# untitled.net
KiCad netlist of a schematic drawn in EAGLE
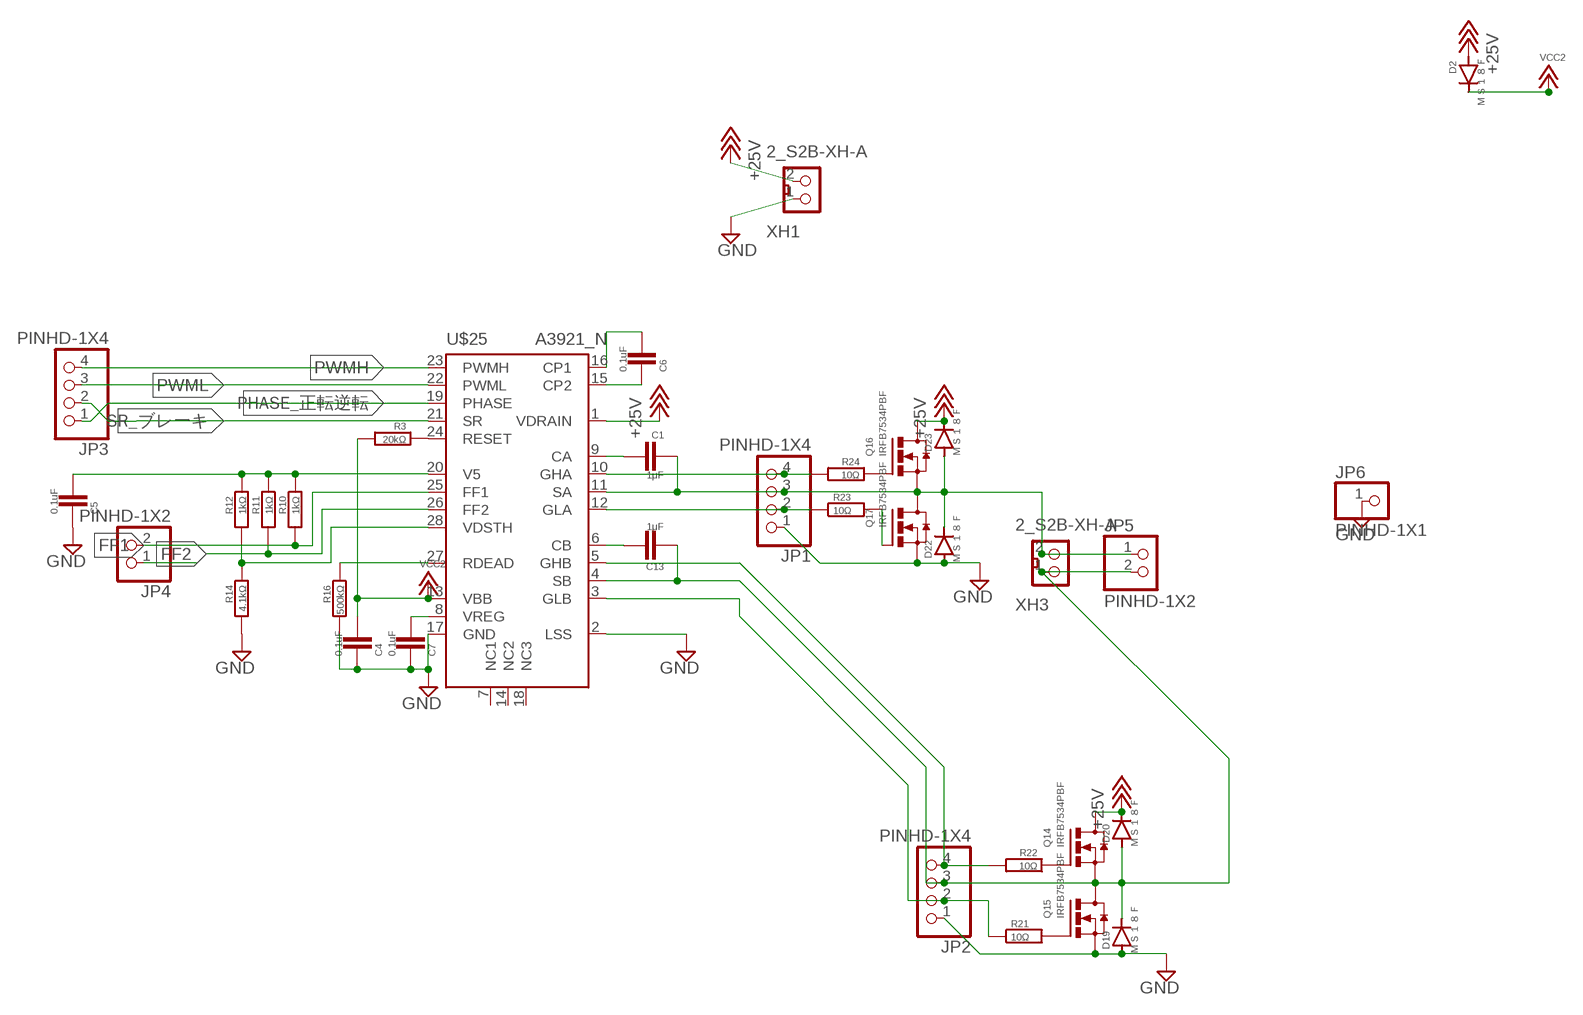
[diagram p0: schematic, sheet 1]

(export (version "E")
  (design (tool "Eeschema 10.0.6"))
  (components
    (comp (ref "C1")
      (value "1μF")
      (footprint "eagle-import:2012")
      (libsource (lib "eagle-import") (part "CAPACITOR{gt}{gt}2012"))
    )
    (comp (ref "C4")
      (value "0.1uF")
      (footprint "eagle-import:2012")
      (libsource (lib "eagle-import") (part "CAPACITOR{gt}{gt}2012"))
    )
    (comp (ref "C5")
      (value "0.1uF")
      (footprint "eagle-import:2012")
      (libsource (lib "eagle-import") (part "CAPACITOR{gt}{gt}2012"))
    )
    (comp (ref "C6")
      (value "0.1uF")
      (footprint "eagle-import:2012")
      (libsource (lib "eagle-import") (part "CAPACITOR{gt}{gt}2012"))
    )
    (comp (ref "C7")
      (value "0.1uF")
      (footprint "eagle-import:2012")
      (libsource (lib "eagle-import") (part "CAPACITOR{gt}{gt}2012"))
    )
    (comp (ref "C13")
      (value "1μF")
      (footprint "eagle-import:2012")
      (libsource (lib "eagle-import") (part "CAPACITOR{gt}{gt}2012"))
    )
    (comp (ref "D2")
      (value "ＭＳ１８Ｆ")
      (footprint "eagle-import:MS18F")
      (libsource (lib "eagle-import") (part "DIODE{gt}{gt}MS18F"))
    )
    (comp (ref "D19")
      (value "ＭＳ１８Ｆ")
      (footprint "eagle-import:MS18F")
      (libsource (lib "eagle-import") (part "DIODE{gt}{gt}MS18F"))
    )
    (comp (ref "D20")
      (value "ＭＳ１８Ｆ")
      (footprint "eagle-import:MS18F")
      (libsource (lib "eagle-import") (part "DIODE{gt}{gt}MS18F"))
    )
    (comp (ref "D22")
      (value "ＭＳ１８Ｆ")
      (footprint "eagle-import:MS18F")
      (libsource (lib "eagle-import") (part "DIODE{gt}{gt}MS18F"))
    )
    (comp (ref "D23")
      (value "ＭＳ１８Ｆ")
      (footprint "eagle-import:MS18F")
      (libsource (lib "eagle-import") (part "DIODE{gt}{gt}MS18F"))
    )
    (comp (ref "JP1")
      (value "PINHD-1X4")
      (footprint "eagle-import:1X04")
      (libsource (lib "eagle-import") (part "PINHD-1X4"))
    )
    (comp (ref "JP2")
      (value "PINHD-1X4")
      (footprint "eagle-import:1X04")
      (libsource (lib "eagle-import") (part "PINHD-1X4"))
    )
    (comp (ref "JP3")
      (value "PINHD-1X4")
      (footprint "eagle-import:1X04")
      (libsource (lib "eagle-import") (part "PINHD-1X4"))
    )
    (comp (ref "JP4")
      (value "PINHD-1X2")
      (footprint "eagle-import:1X02")
      (libsource (lib "eagle-import") (part "PINHD-1X2"))
    )
    (comp (ref "JP5")
      (value "PINHD-1X2")
      (footprint "eagle-import:1X02")
      (libsource (lib "eagle-import") (part "PINHD-1X2"))
    )
    (comp (ref "JP6")
      (value "PINHD-1X1")
      (footprint "eagle-import:1X01")
      (libsource (lib "eagle-import") (part "PINHD-1X1"))
    )
    (comp (ref "Q14")
      (value "IRFB7534PBF")
      (footprint "eagle-import:TO252")
      (libsource (lib "eagle-import") (part "MOSFET_N{gt}{gt}TO252"))
    )
    (comp (ref "Q15")
      (value "IRFB7534PBF")
      (footprint "eagle-import:TO252")
      (libsource (lib "eagle-import") (part "MOSFET_N{gt}{gt}TO252"))
    )
    (comp (ref "Q16")
      (value "IRFB7534PBF")
      (footprint "eagle-import:TO252")
      (libsource (lib "eagle-import") (part "MOSFET_N{gt}{gt}TO252"))
    )
    (comp (ref "Q17")
      (value "IRFB7534PBF")
      (footprint "eagle-import:TO252")
      (libsource (lib "eagle-import") (part "MOSFET_N{gt}{gt}TO252"))
    )
    (comp (ref "R3")
      (value "20kΩ")
      (footprint "eagle-import:2012")
      (libsource (lib "eagle-import") (part "REGISTER{gt}{gt}2012"))
    )
    (comp (ref "R10")
      (value "1kΩ")
      (footprint "eagle-import:2012")
      (libsource (lib "eagle-import") (part "REGISTER{gt}{gt}2012"))
    )
    (comp (ref "R11")
      (value "1kΩ")
      (footprint "eagle-import:2012")
      (libsource (lib "eagle-import") (part "REGISTER{gt}{gt}2012"))
    )
    (comp (ref "R12")
      (value "1kΩ")
      (footprint "eagle-import:2012")
      (libsource (lib "eagle-import") (part "REGISTER{gt}{gt}2012"))
    )
    (comp (ref "R14")
      (value "4.1kΩ")
      (footprint "eagle-import:2012")
      (libsource (lib "eagle-import") (part "REGISTER{gt}{gt}2012"))
    )
    (comp (ref "R16")
      (value "500kΩ")
      (footprint "eagle-import:2012")
      (libsource (lib "eagle-import") (part "REGISTER{gt}{gt}2012"))
    )
    (comp (ref "R21")
      (value "10Ω")
      (footprint "eagle-import:2012")
      (libsource (lib "eagle-import") (part "REGISTER{gt}{gt}2012"))
    )
    (comp (ref "R22")
      (value "10Ω")
      (footprint "eagle-import:2012")
      (libsource (lib "eagle-import") (part "REGISTER{gt}{gt}2012"))
    )
    (comp (ref "R23")
      (value "10Ω")
      (footprint "eagle-import:2012")
      (libsource (lib "eagle-import") (part "REGISTER{gt}{gt}2012"))
    )
    (comp (ref "R24")
      (value "10Ω")
      (footprint "eagle-import:2012")
      (libsource (lib "eagle-import") (part "REGISTER{gt}{gt}2012"))
    )
    (comp (ref "U$25")
      (value "A3921_N")
      (footprint "eagle-import:TSSOP28_N")
      (libsource (lib "eagle-import") (part "A3921_N"))
    )
    (comp (ref "XH1")
      (value "2_S2B-XH-A")
      (footprint "eagle-import:S2B-XH-A")
      (libsource (lib "eagle-import") (part "2_S2B-XH-A"))
    )
    (comp (ref "XH3")
      (value "2_S2B-XH-A")
      (footprint "eagle-import:S2B-XH-A")
      (libsource (lib "eagle-import") (part "2_S2B-XH-A"))
    )
  )
  (nets
    (net (code "1") (name "+25V") (class "Default")
      (node (ref "D2") (pin "P$1") (pinfunction "A_P$1") (pintype "passive"))
      (node (ref "D20") (pin "P$2") (pinfunction "C_P$2") (pintype "passive"))
      (node (ref "D23") (pin "P$2") (pinfunction "C_P$2") (pintype "passive"))
      (node (ref "Q14") (pin "3") (pinfunction "D_3") (pintype "passive"))
      (node (ref "Q16") (pin "3") (pinfunction "D_3") (pintype "passive"))
      (node (ref "U$25") (pin "1") (pinfunction "VDRAIN_1") (pintype "power_in"))
      (node (ref "XH1") (pin "2") (pinfunction "2_2") (pintype "passive"))
    )
    (net (code "2") (name "FF1") (class "Default")
      (node (ref "JP4") (pin "2") (pinfunction "2_2") (pintype "passive"))
      (node (ref "R10") (pin "2") (pinfunction "2_2") (pintype "passive"))
      (node (ref "U$25") (pin "25") (pinfunction "FF1_25") (pintype "output"))
    )
    (net (code "3") (name "FF2") (class "Default")
      (node (ref "JP4") (pin "1") (pinfunction "1_1") (pintype "passive"))
      (node (ref "R11") (pin "2") (pinfunction "2_2") (pintype "passive"))
      (node (ref "U$25") (pin "26") (pinfunction "FF2_26") (pintype "output"))
    )
    (net (code "4") (name "GND") (class "Default")
      (node (ref "C4") (pin "2") (pinfunction "2_2") (pintype "passive"))
      (node (ref "C5") (pin "2") (pinfunction "2_2") (pintype "passive"))
      (node (ref "C7") (pin "2") (pinfunction "2_2") (pintype "passive"))
      (node (ref "D19") (pin "P$1") (pinfunction "A_P$1") (pintype "passive"))
      (node (ref "D22") (pin "P$1") (pinfunction "A_P$1") (pintype "passive"))
      (node (ref "JP1") (pin "1") (pinfunction "1_1") (pintype "passive"))
      (node (ref "JP2") (pin "1") (pinfunction "1_1") (pintype "passive"))
      (node (ref "JP6") (pin "1") (pinfunction "1_1") (pintype "passive"))
      (node (ref "Q15") (pin "2") (pinfunction "S_2") (pintype "passive"))
      (node (ref "Q17") (pin "2") (pinfunction "S_2") (pintype "passive"))
      (node (ref "R14") (pin "2") (pinfunction "2_2") (pintype "passive"))
      (node (ref "R16") (pin "2") (pinfunction "2_2") (pintype "passive"))
      (node (ref "U$25") (pin "17") (pinfunction "GND_17") (pintype "power_in"))
      (node (ref "U$25") (pin "2") (pinfunction "LSS_2") (pintype "passive"))
      (node (ref "XH1") (pin "1") (pinfunction "1_1") (pintype "passive"))
    )
    (net (code "5") (name "Net-(D19-C)") (class "Default")
      (node (ref "C13") (pin "2") (pinfunction "2_2") (pintype "passive"))
      (node (ref "D19") (pin "P$2") (pinfunction "C_P$2") (pintype "passive"))
      (node (ref "D20") (pin "P$1") (pinfunction "A_P$1") (pintype "passive"))
      (node (ref "JP2") (pin "3") (pinfunction "3_3") (pintype "passive"))
      (node (ref "JP5") (pin "2") (pinfunction "2_2") (pintype "passive"))
      (node (ref "Q14") (pin "2") (pinfunction "S_2") (pintype "passive"))
      (node (ref "Q15") (pin "3") (pinfunction "D_3") (pintype "passive"))
      (node (ref "U$25") (pin "4") (pinfunction "SB_4") (pintype "output"))
      (node (ref "XH3") (pin "1") (pinfunction "1_1") (pintype "passive"))
    )
    (net (code "6") (name "Net-(D22-C)") (class "Default")
      (node (ref "C1") (pin "2") (pinfunction "2_2") (pintype "passive"))
      (node (ref "D22") (pin "P$2") (pinfunction "C_P$2") (pintype "passive"))
      (node (ref "D23") (pin "P$1") (pinfunction "A_P$1") (pintype "passive"))
      (node (ref "JP1") (pin "3") (pinfunction "3_3") (pintype "passive"))
      (node (ref "JP5") (pin "1") (pinfunction "1_1") (pintype "passive"))
      (node (ref "Q16") (pin "2") (pinfunction "S_2") (pintype "passive"))
      (node (ref "Q17") (pin "3") (pinfunction "D_3") (pintype "passive"))
      (node (ref "U$25") (pin "11") (pinfunction "SA_11") (pintype "output"))
      (node (ref "XH3") (pin "2") (pinfunction "2_2") (pintype "passive"))
    )
    (net (code "7") (name "Net-(Q14-G)") (class "Default")
      (node (ref "Q14") (pin "1") (pinfunction "G_1") (pintype "passive"))
      (node (ref "R22") (pin "1") (pinfunction "1_1") (pintype "passive"))
    )
    (net (code "8") (name "Net-(Q15-G)") (class "Default")
      (node (ref "Q15") (pin "1") (pinfunction "G_1") (pintype "passive"))
      (node (ref "R21") (pin "2") (pinfunction "2_2") (pintype "passive"))
    )
    (net (code "9") (name "Net-(Q16-G)") (class "Default")
      (node (ref "Q16") (pin "1") (pinfunction "G_1") (pintype "passive"))
      (node (ref "R24") (pin "1") (pinfunction "1_1") (pintype "passive"))
    )
    (net (code "10") (name "Net-(Q17-G)") (class "Default")
      (node (ref "Q17") (pin "1") (pinfunction "G_1") (pintype "passive"))
      (node (ref "R23") (pin "2") (pinfunction "2_2") (pintype "passive"))
    )
    (net (code "11") (name "Net-(U$25-CA)") (class "Default")
      (node (ref "C1") (pin "1") (pinfunction "1_1") (pintype "passive"))
      (node (ref "U$25") (pin "9") (pinfunction "CA_9") (pintype "input"))
    )
    (net (code "12") (name "Net-(U$25-CB)") (class "Default")
      (node (ref "C13") (pin "1") (pinfunction "1_1") (pintype "passive"))
      (node (ref "U$25") (pin "6") (pinfunction "CB_6") (pintype "input"))
    )
    (net (code "13") (name "Net-(U$25-CP1)") (class "Default")
      (node (ref "C6") (pin "1") (pinfunction "1_1") (pintype "passive"))
      (node (ref "U$25") (pin "16") (pinfunction "CP1_16") (pintype "passive"))
    )
    (net (code "14") (name "Net-(U$25-CP2)") (class "Default")
      (node (ref "C6") (pin "2") (pinfunction "2_2") (pintype "passive"))
      (node (ref "U$25") (pin "15") (pinfunction "CP2_15") (pintype "passive"))
    )
    (net (code "15") (name "Net-(U$25-GHA)") (class "Default")
      (node (ref "JP1") (pin "4") (pinfunction "4_4") (pintype "passive"))
      (node (ref "R24") (pin "2") (pinfunction "2_2") (pintype "passive"))
      (node (ref "U$25") (pin "10") (pinfunction "GHA_10") (pintype "output"))
    )
    (net (code "16") (name "Net-(U$25-GHB)") (class "Default")
      (node (ref "JP2") (pin "4") (pinfunction "4_4") (pintype "passive"))
      (node (ref "R22") (pin "2") (pinfunction "2_2") (pintype "passive"))
      (node (ref "U$25") (pin "5") (pinfunction "GHB_5") (pintype "output"))
    )
    (net (code "17") (name "Net-(U$25-GLA)") (class "Default")
      (node (ref "JP1") (pin "2") (pinfunction "2_2") (pintype "passive"))
      (node (ref "R23") (pin "1") (pinfunction "1_1") (pintype "passive"))
      (node (ref "U$25") (pin "12") (pinfunction "GLA_12") (pintype "output"))
    )
    (net (code "18") (name "Net-(U$25-GLB)") (class "Default")
      (node (ref "JP2") (pin "2") (pinfunction "2_2") (pintype "passive"))
      (node (ref "R21") (pin "1") (pinfunction "1_1") (pintype "passive"))
      (node (ref "U$25") (pin "3") (pinfunction "GLB_3") (pintype "output"))
    )
    (net (code "19") (name "Net-(U$25-RDEAD)") (class "Default")
      (node (ref "R16") (pin "1") (pinfunction "1_1") (pintype "passive"))
      (node (ref "U$25") (pin "27") (pinfunction "RDEAD_27") (pintype "input"))
    )
    (net (code "20") (name "Net-(U$25-RESET)") (class "Default")
      (node (ref "R3") (pin "1") (pinfunction "1_1") (pintype "passive"))
      (node (ref "U$25") (pin "24") (pinfunction "RESET_24") (pintype "input"))
    )
    (net (code "21") (name "Net-(U$25-V5)") (class "Default")
      (node (ref "C5") (pin "1") (pinfunction "1_1") (pintype "passive"))
      (node (ref "R10") (pin "1") (pinfunction "1_1") (pintype "passive"))
      (node (ref "R11") (pin "1") (pinfunction "1_1") (pintype "passive"))
      (node (ref "R12") (pin "1") (pinfunction "1_1") (pintype "passive"))
      (node (ref "U$25") (pin "20") (pinfunction "V5_20") (pintype "power_in"))
    )
    (net (code "22") (name "Net-(U$25-VDSTH)") (class "Default")
      (node (ref "R12") (pin "2") (pinfunction "2_2") (pintype "passive"))
      (node (ref "R14") (pin "1") (pinfunction "1_1") (pintype "passive"))
      (node (ref "U$25") (pin "28") (pinfunction "VDSTH_28") (pintype "input"))
    )
    (net (code "23") (name "Net-(U$25-VREG)") (class "Default")
      (node (ref "C7") (pin "1") (pinfunction "1_1") (pintype "passive"))
      (node (ref "U$25") (pin "8") (pinfunction "VREG_8") (pintype "power_in"))
    )
    (net (code "24") (name "PHASE_正転逆転") (class "Default")
      (node (ref "JP3") (pin "1") (pinfunction "1_1") (pintype "passive"))
      (node (ref "U$25") (pin "19") (pinfunction "PHASE_19") (pintype "input"))
    )
    (net (code "25") (name "PWMH") (class "Default")
      (node (ref "JP3") (pin "4") (pinfunction "4_4") (pintype "passive"))
      (node (ref "U$25") (pin "23") (pinfunction "PWMH_23") (pintype "input"))
    )
    (net (code "26") (name "PWML") (class "Default")
      (node (ref "JP3") (pin "3") (pinfunction "3_3") (pintype "passive"))
      (node (ref "U$25") (pin "22") (pinfunction "PWML_22") (pintype "input"))
    )
    (net (code "27") (name "SR_ブレーキ") (class "Default")
      (node (ref "JP3") (pin "2") (pinfunction "2_2") (pintype "passive"))
      (node (ref "U$25") (pin "21") (pinfunction "SR_21") (pintype "input"))
    )
    (net (code "28") (name "VCC2") (class "Default")
      (node (ref "C4") (pin "1") (pinfunction "1_1") (pintype "passive"))
      (node (ref "D2") (pin "P$2") (pinfunction "C_P$2") (pintype "passive"))
      (node (ref "R3") (pin "2") (pinfunction "2_2") (pintype "passive"))
      (node (ref "U$25") (pin "13") (pinfunction "VBB_13") (pintype "power_in"))
    )
    (net (code "29") (name "unconnected-(U$25-NC1-Pad7)") (class "Default")
      (node (ref "U$25") (pin "7") (pinfunction "NC1_7") (pintype "no_connect"))
    )
    (net (code "30") (name "unconnected-(U$25-NC2-Pad14)") (class "Default")
      (node (ref "U$25") (pin "14") (pinfunction "NC2_14") (pintype "no_connect"))
    )
    (net (code "31") (name "unconnected-(U$25-NC3-Pad18)") (class "Default")
      (node (ref "U$25") (pin "18") (pinfunction "NC3_18") (pintype "no_connect"))
    )
  )
)
